# FunctionalSchematic.net
KiCad netlist of a schematic drawn in Altium Designer
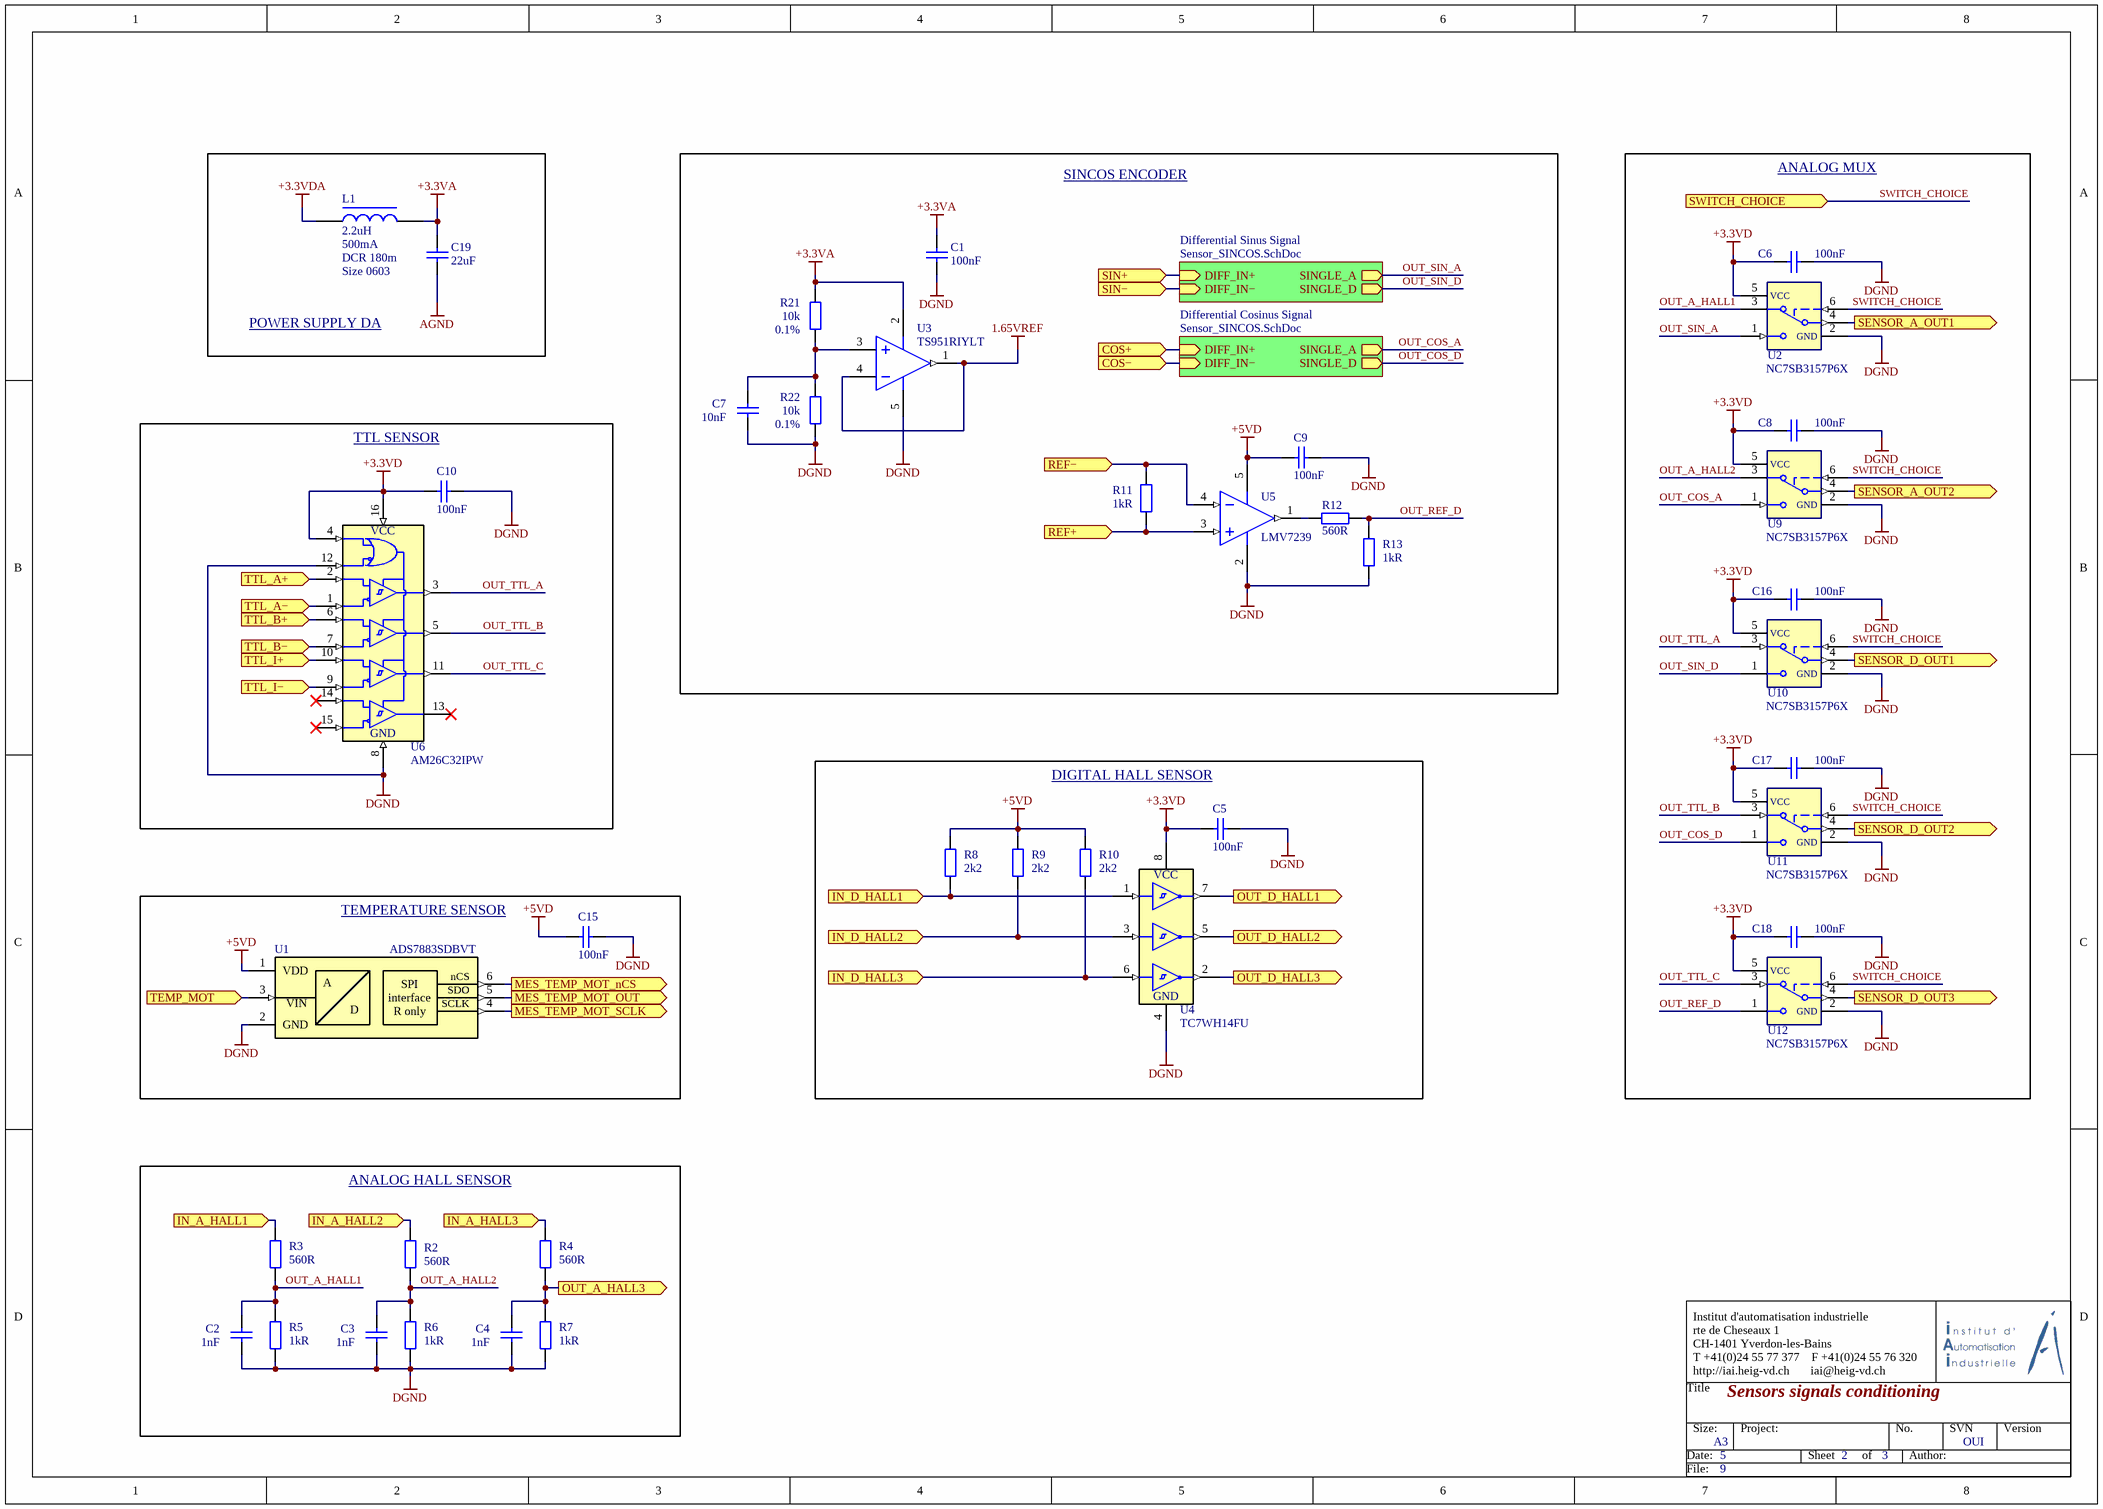
[diagram p0: FunctionalSchematic.SchDoc]

(export (version "E")
  (design (tool "Eeschema 10.0.6"))
  (components
    (comp (ref "C1")
      (value "100nF")
      (footprint "InterfaceBoard:CAPC1608X08N")
      (fields (field (name "Comment") "CAP CER 0603"))
      (libsource (lib "InterfaceBoard") (part "CAP CER 100nF 10% 10V 0603"))
    )
    (comp (ref "C2")
      (value "1nF")
      (footprint "InterfaceBoard:CAPC1608X08N")
      (description "1nF ±10% 10V Condensateurs céramique X7R 0603 (1608 métrique)")
      (fields (field (name "Comment") "CAP CER 1nF 0603"))
      (libsource (lib "InterfaceBoard") (part "CAP CER 1nF 10% 10V 0603"))
    )
    (comp (ref "C3")
      (value "1nF")
      (footprint "InterfaceBoard:CAPC1608X08N")
      (description "1nF ±10% 10V Condensateurs céramique X7R 0603 (1608 métrique)")
      (fields (field (name "Comment") "CAP CER 1nF 0603"))
      (libsource (lib "InterfaceBoard") (part "CAP CER 1nF 10% 10V 0603"))
    )
    (comp (ref "C4")
      (value "1nF")
      (footprint "InterfaceBoard:CAPC1608X08N")
      (description "1nF ±10% 10V Condensateurs céramique X7R 0603 (1608 métrique)")
      (fields (field (name "Comment") "CAP CER 1nF 0603"))
      (libsource (lib "InterfaceBoard") (part "CAP CER 1nF 10% 10V 0603"))
    )
    (comp (ref "C5")
      (value "100nF")
      (footprint "InterfaceBoard:CAPC1608X08N")
      (description "100nF ±10% 10V Condensateurs céramique X7R 0603 (1608 métrique)")
      (fields (field (name "Comment") "CAP CER 100nF 0603"))
      (libsource (lib "InterfaceBoard") (part "CAP CER 100nF 10% 10V 0603"))
    )
    (comp (ref "C6")
      (value "100nF")
      (footprint "InterfaceBoard:CAPC1608X08N")
      (description "100nF ±10% 10V Condensateurs céramique X7R 0603 (1608 métrique)")
      (fields (field (name "Comment") "CAP CER 100nF 0603"))
      (libsource (lib "InterfaceBoard") (part "CAP CER 100nF 10% 10V 0603"))
    )
    (comp (ref "C7")
      (value "10nF")
      (footprint "InterfaceBoard:CAPC1608X08N")
      (fields (field (name "Comment") "CAP CER 0603"))
      (libsource (lib "InterfaceBoard") (part "CAP CER 10nF 10% 10V 0603"))
    )
    (comp (ref "C8")
      (value "100nF")
      (footprint "InterfaceBoard:CAPC1608X08N")
      (description "100nF ±10% 10V Condensateurs céramique X7R 0603 (1608 métrique)")
      (fields (field (name "Comment") "CAP CER 100nF 0603"))
      (libsource (lib "InterfaceBoard") (part "CAP CER 100nF 10% 10V 0603"))
    )
    (comp (ref "C9")
      (value "100nF")
      (footprint "InterfaceBoard:CAPC1608X08N")
      (description "100nF ±10% 10V Condensateurs céramique X7R 0603 (1608 métrique)")
      (fields (field (name "Comment") "CAP CER 100nF 0603"))
      (libsource (lib "InterfaceBoard") (part "CAP CER 100nF 10% 10V 0603"))
    )
    (comp (ref "C10")
      (value "100nF")
      (footprint "InterfaceBoard:CAPC1608X08N")
      (description "100nF ±10% 10V Condensateurs céramique X7R 0603 (1608 métrique)")
      (fields (field (name "Comment") "CAP CER 100nF 0603"))
      (libsource (lib "InterfaceBoard") (part "CAP CER 100nF 10% 10V 0603"))
    )
    (comp (ref "C15")
      (value "100nF")
      (footprint "InterfaceBoard:CAPC1608X08N")
      (description "100nF ±10% 10V Condensateurs céramique X7R 0603 (1608 métrique)")
      (fields (field (name "Comment") "CAP CER 100nF 0603"))
      (libsource (lib "InterfaceBoard") (part "CAP CER 100nF 10% 10V 0603"))
    )
    (comp (ref "C16")
      (value "100nF")
      (footprint "InterfaceBoard:CAPC1608X08N")
      (description "100nF ±10% 10V Condensateurs céramique X7R 0603 (1608 métrique)")
      (fields (field (name "Comment") "CAP CER 100nF 0603"))
      (libsource (lib "InterfaceBoard") (part "CAP CER 100nF 10% 10V 0603"))
    )
    (comp (ref "C17")
      (value "100nF")
      (footprint "InterfaceBoard:CAPC1608X08N")
      (description "100nF ±10% 10V Condensateurs céramique X7R 0603 (1608 métrique)")
      (fields (field (name "Comment") "CAP CER 100nF 0603"))
      (libsource (lib "InterfaceBoard") (part "CAP CER 100nF 10% 10V 0603"))
    )
    (comp (ref "C18")
      (value "100nF")
      (footprint "InterfaceBoard:CAPC1608X08N")
      (description "100nF ±10% 10V Condensateurs céramique X7R 0603 (1608 métrique)")
      (fields (field (name "Comment") "CAP CER 100nF 0603"))
      (libsource (lib "InterfaceBoard") (part "CAP CER 100nF 10% 10V 0603"))
    )
    (comp (ref "C19")
      (value "22uF")
      (footprint "PowerBoard:CAPC1608X08N")
      (description "22µF ±20% 6,3V Condensateurs céramique X5R 0603 (1608 métrique)")
      (fields (field (name "Comment") "CAP CER 22uF 0603"))
      (libsource (lib "PowerBoard") (part "CAP CER 22uF 20% 6V3 0603"))
    )
    (comp (ref "L1")
      (value "2.2uH")
      (footprint "InterfaceBoard:INDC1608X10N")
      (fields
        (field (name "CURRENT") "500mA")
        (field (name "DCR") "DCR 180m")
        (field (name "SIZE") "Size 0603")
        (field (name "Comment") "IND SMD 2.2uH 0603")
      )
      (libsource (lib "CommandBoard") (part "IND SMD 2.2uH 0603"))
    )
    (comp (ref "R2")
      (value "560R")
      (footprint "InterfaceBoard:RESC1508X04N")
      (description "560 Ohms ±1% 0,1W, 1/10W Pavé résistif 0603 (1608 métrique) AutomobileAEC-Q200 Couche épaisse")
      (fields (field (name "Comment") "RES SMD 560R 0603"))
      (libsource (lib "InterfaceBoard") (part "RES SMD 560 OHM 0.1% 1/10W 0603"))
    )
    (comp (ref "R3")
      (value "560R")
      (footprint "InterfaceBoard:RESC1508X04N")
      (description "560 Ohms ±1% 0,1W, 1/10W Pavé résistif 0603 (1608 métrique) AutomobileAEC-Q200 Couche épaisse")
      (fields (field (name "Comment") "RES SMD 560R 0603"))
      (libsource (lib "InterfaceBoard") (part "RES SMD 560 OHM 0.1% 1/10W 0603"))
    )
    (comp (ref "R4")
      (value "560R")
      (footprint "InterfaceBoard:RESC1508X04N")
      (description "560 Ohms ±1% 0,1W, 1/10W Pavé résistif 0603 (1608 métrique) AutomobileAEC-Q200 Couche épaisse")
      (fields (field (name "Comment") "RES SMD 560R 0603"))
      (libsource (lib "InterfaceBoard") (part "RES SMD 560 OHM 0.1% 1/10W 0603"))
    )
    (comp (ref "R5")
      (value "1kR")
      (footprint "InterfaceBoard:RESC1508X04N")
      (description "1 kOhms ±1% 0,1W, 1/10W Pavé résistif 0603 (1608 métrique) AutomobileAEC-Q200 Couche épaisse")
      (fields (field (name "Comment") "RES SMD 1K 0603"))
      (libsource (lib "InterfaceBoard") (part "RES SMD 1K OHM 1% 1/10W 0603"))
    )
    (comp (ref "R6")
      (value "1kR")
      (footprint "InterfaceBoard:RESC1508X04N")
      (description "1 kOhms ±1% 0,1W, 1/10W Pavé résistif 0603 (1608 métrique) AutomobileAEC-Q200 Couche épaisse")
      (fields (field (name "Comment") "RES SMD 1K 0603"))
      (libsource (lib "InterfaceBoard") (part "RES SMD 1K OHM 1% 1/10W 0603"))
    )
    (comp (ref "R7")
      (value "1kR")
      (footprint "InterfaceBoard:RESC1508X04N")
      (description "1 kOhms ±1% 0,1W, 1/10W Pavé résistif 0603 (1608 métrique) AutomobileAEC-Q200 Couche épaisse")
      (fields (field (name "Comment") "RES SMD 1K 0603"))
      (libsource (lib "InterfaceBoard") (part "RES SMD 1K OHM 1% 1/10W 0603"))
    )
    (comp (ref "R8")
      (value "2k2")
      (footprint "InterfaceBoard:RESC1508X04N")
      (description "2,2 kOhms ±1% 0,1W, 1/10W Pavé résistif 0603 (1608 métrique) AutomobileAEC-Q200 Couche épaisse")
      (fields (field (name "Comment") "RES SMD 2K2 0603"))
      (libsource (lib "InterfaceBoard") (part "RES SMD 2K2 OHM 1% 1/10W 0603"))
    )
    (comp (ref "R9")
      (value "2k2")
      (footprint "InterfaceBoard:RESC1508X04N")
      (description "2,2 kOhms ±1% 0,1W, 1/10W Pavé résistif 0603 (1608 métrique) AutomobileAEC-Q200 Couche épaisse")
      (fields (field (name "Comment") "RES SMD 2K2 0603"))
      (libsource (lib "InterfaceBoard") (part "RES SMD 2K2 OHM 1% 1/10W 0603"))
    )
    (comp (ref "R10")
      (value "2k2")
      (footprint "InterfaceBoard:RESC1508X04N")
      (description "2,2 kOhms ±1% 0,1W, 1/10W Pavé résistif 0603 (1608 métrique) AutomobileAEC-Q200 Couche épaisse")
      (fields (field (name "Comment") "RES SMD 2K2 0603"))
      (libsource (lib "InterfaceBoard") (part "RES SMD 2K2 OHM 1% 1/10W 0603"))
    )
    (comp (ref "R11")
      (value "1kR")
      (footprint "InterfaceBoard:RESC1508X04N")
      (description "1 kOhms ±1% 0,1W, 1/10W Pavé résistif 0603 (1608 métrique) AutomobileAEC-Q200 Couche épaisse")
      (fields (field (name "Comment") "RES SMD 1K 0603"))
      (libsource (lib "") (part "RES SMD 1K OHM 1% 1/10W 0603_1"))
    )
    (comp (ref "R12")
      (value "560R")
      (footprint "InterfaceBoard:RESC1508X04N")
      (description "560 Ohms ±1% 0,1W, 1/10W Pavé résistif 0603 (1608 métrique) AutomobileAEC-Q200 Couche épaisse")
      (fields (field (name "Comment") "RES SMD 560R 0603"))
      (libsource (lib "") (part "RES SMD 560 OHM 0.1% 1/10W 0603_1"))
    )
    (comp (ref "R13")
      (value "1kR")
      (footprint "InterfaceBoard:RESC1508X04N")
      (description "1 kOhms ±1% 0,1W, 1/10W Pavé résistif 0603 (1608 métrique) AutomobileAEC-Q200 Couche épaisse")
      (fields (field (name "Comment") "RES SMD 1K 0603"))
      (libsource (lib "InterfaceBoard") (part "RES SMD 1K OHM 1% 1/10W 0603"))
    )
    (comp (ref "R21")
      (value "10k")
      (footprint "InterfaceBoard:RESC1508X04N")
      (description "10 kOhms ±0,1% 0,1W, 1/10W Pavé résistif 0603 (1608 métrique) AutomobileAEC-Q200 Couche mince")
      (fields (field (name "TOLERANCE") "0.1%") (field (name "Comment") "RES SMD 0603"))
      (libsource (lib "InterfaceBoard") (part "RES SMD 10K OHM 1% 1/10W 0603"))
    )
    (comp (ref "R22")
      (value "10k")
      (footprint "InterfaceBoard:RESC1508X04N")
      (description "10 kOhms ±0,1% 0,1W, 1/10W Pavé résistif 0603 (1608 métrique) AutomobileAEC-Q200 Couche mince")
      (fields (field (name "TOLERANCE") "0.1%") (field (name "Comment") "RES SMD 0603"))
      (libsource (lib "InterfaceBoard") (part "RES SMD 10K OHM 1% 1/10W 0603"))
    )
    (comp (ref "U1")
      (value "ADS7883SDBVT")
      (footprint "InterfaceBoard:SOT95P280X145-6N")
      (description "12 Bits, convertisseur analogique-numérique 1 Entrée 1 SAR SOT-23-6")
      (fields (field (name "Comment") "IC ADC 12BIT"))
      (libsource (lib "InterfaceBoard") (part "IC ADC 12BIT SAR SOT23-6"))
    )
    (comp (ref "U2")
      (value "NC7SB3157P6X")
      (footprint "InterfaceBoard:SOT95P280X145-6N")
      (description "1 Circuits, circuit intégré, commutateur 2:1 15Ohms SC-88 (SC-70-6)")
      (fields (field (name "Comment") "Analog Switch 2:1 1ch"))
      (libsource (lib "InterfaceBoard") (part "IC SWITCH SPDT"))
    )
    (comp (ref "U3")
      (value "TS951RIYLT")
      (footprint "InterfaceBoard:SOT95P280X145-5N")
      (description "CMOS Amplificateurs 1 Circuits Pôle à pôle SOT-23-5")
      (fields (field (name "Comment") "OPAMP 1 CIRCUIT"))
      (libsource (lib "InterfaceBoard") (part "IC OPAMP GP 1 CIRCUIT SOT23-5"))
    )
    (comp (ref "U4")
      (value "TC7WH14FU")
      (footprint "InterfaceBoard:TSSOP50P310X100-8N")
      (description "Inverseur IC 3 Canal US8")
      (fields (field (name "Comment") "IC INVERTER 3CH"))
      (libsource (lib "InterfaceBoard") (part "IC INVERTER 3CH 3-INP US8"))
    )
    (comp (ref "U5")
      (value "LMV7239")
      (footprint "InterfaceBoard:SOT95P280X145-5N")
      (description "Comparateurs Usage général Pousser-tirer, rail-à-rail SOT-23-5")
      (fields (field (name "Comment") "COMP 1 CIRCUIT"))
      (libsource (lib "InterfaceBoard") (part "IC COMP PUSH-PULL 1 CIRCUIT SOT-23-5"))
    )
    (comp (ref "U6")
      (value "AM26C32IPW")
      (footprint "InterfaceBoard:TSOP65P640X120-16N")
      (description "Récepteur 0/4 RS422, RS423 16-TSSOP")
      (fields (field (name "Comment") "IC RECEIVER 0/4"))
      (libsource (lib "InterfaceBoard") (part "IC RECEIVER 0/4 16TSSOP"))
    )
    (comp (ref "U9")
      (value "NC7SB3157P6X")
      (footprint "InterfaceBoard:SOT95P280X145-6N")
      (description "1 Circuits, circuit intégré, commutateur 2:1 15Ohms SC-88 (SC-70-6)")
      (fields (field (name "Comment") "Analog Switch 2:1 1ch"))
      (libsource (lib "InterfaceBoard") (part "IC SWITCH SPDT"))
    )
    (comp (ref "U10")
      (value "NC7SB3157P6X")
      (footprint "InterfaceBoard:SOT95P280X145-6N")
      (description "1 Circuits, circuit intégré, commutateur 2:1 15Ohms SC-88 (SC-70-6)")
      (fields (field (name "Comment") "Analog Switch 2:1 1ch"))
      (libsource (lib "InterfaceBoard") (part "IC SWITCH SPDT"))
    )
    (comp (ref "U11")
      (value "NC7SB3157P6X")
      (footprint "InterfaceBoard:SOT95P280X145-6N")
      (description "1 Circuits, circuit intégré, commutateur 2:1 15Ohms SC-88 (SC-70-6)")
      (fields (field (name "Comment") "Analog Switch 2:1 1ch"))
      (libsource (lib "InterfaceBoard") (part "IC SWITCH SPDT"))
    )
    (comp (ref "U12")
      (value "NC7SB3157P6X")
      (footprint "InterfaceBoard:SOT95P280X145-6N")
      (description "1 Circuits, circuit intégré, commutateur 2:1 15Ohms SC-88 (SC-70-6)")
      (fields (field (name "Comment") "Analog Switch 2:1 1ch"))
      (libsource (lib "InterfaceBoard") (part "IC SWITCH SPDT"))
    )
  )
  (nets
    (net (code "1") (name "+3.3VA") (class "Default")
      (node (ref "C1") (pin "1") (pinfunction "1_1") (pintype "passive"))
      (node (ref "C19") (pin "2") (pinfunction "2_2") (pintype "passive"))
      (node (ref "L1") (pin "2") (pinfunction "2_2") (pintype "passive"))
      (node (ref "R21") (pin "2") (pinfunction "2_2") (pintype "passive"))
      (node (ref "U3") (pin "2") (pinfunction "IN-_2") (pintype "power_in"))
    )
    (net (code "2") (name "+3.3VD") (class "Default")
      (node (ref "C10") (pin "2") (pinfunction "2_2") (pintype "passive"))
      (node (ref "C16") (pin "1") (pinfunction "1_1") (pintype "passive"))
      (node (ref "C17") (pin "1") (pinfunction "1_1") (pintype "passive"))
      (node (ref "C18") (pin "1") (pinfunction "1_1") (pintype "passive"))
      (node (ref "C5") (pin "2") (pinfunction "2_2") (pintype "passive"))
      (node (ref "C6") (pin "1") (pinfunction "1_1") (pintype "passive"))
      (node (ref "C8") (pin "1") (pinfunction "1_1") (pintype "passive"))
      (node (ref "U10") (pin "5") (pinfunction "VCC_5") (pintype "power_in"))
      (node (ref "U11") (pin "5") (pinfunction "VCC_5") (pintype "power_in"))
      (node (ref "U12") (pin "5") (pinfunction "VCC_5") (pintype "power_in"))
      (node (ref "U2") (pin "5") (pinfunction "VCC_5") (pintype "power_in"))
      (node (ref "U4") (pin "8") (pintype "power_in"))
      (node (ref "U6") (pin "16") (pintype "input"))
      (node (ref "U6") (pin "4") (pintype "input"))
      (node (ref "U9") (pin "5") (pinfunction "VCC_5") (pintype "power_in"))
    )
    (net (code "3") (name "+3.3VDA") (class "Default")
      (node (ref "L1") (pin "1") (pinfunction "1_1") (pintype "passive"))
    )
    (net (code "4") (name "+5VD") (class "Default")
      (node (ref "C15") (pin "2") (pinfunction "2_2") (pintype "passive"))
      (node (ref "C9") (pin "1") (pinfunction "1_1") (pintype "passive"))
      (node (ref "R10") (pin "2") (pinfunction "2_2") (pintype "passive"))
      (node (ref "R8") (pin "2") (pinfunction "2_2") (pintype "passive"))
      (node (ref "R9") (pin "2") (pinfunction "2_2") (pintype "passive"))
      (node (ref "U1") (pin "1") (pinfunction "VDD_1") (pintype "power_in"))
      (node (ref "U5") (pin "5") (pinfunction "IN-_5") (pintype "power_in"))
    )
    (net (code "7") (name "/IN_A_HALL1") (class "Default")
      (node (ref "R3") (pin "2") (pinfunction "2_2") (pintype "passive"))
    )
    (net (code "8") (name "/IN_A_HALL2") (class "Default")
      (node (ref "R2") (pin "2") (pinfunction "2_2") (pintype "passive"))
    )
    (net (code "9") (name "/IN_A_HALL3") (class "Default")
      (node (ref "R4") (pin "2") (pinfunction "2_2") (pintype "passive"))
    )
    (net (code "10") (name "/IN_D_HALL1") (class "Default")
      (node (ref "R8") (pin "1") (pinfunction "1_1") (pintype "passive"))
      (node (ref "U4") (pin "1") (pintype "input"))
    )
    (net (code "11") (name "/IN_D_HALL2") (class "Default")
      (node (ref "R9") (pin "1") (pinfunction "1_1") (pintype "passive"))
      (node (ref "U4") (pin "3") (pintype "input"))
    )
    (net (code "12") (name "/IN_D_HALL3") (class "Default")
      (node (ref "R10") (pin "1") (pinfunction "1_1") (pintype "passive"))
      (node (ref "U4") (pin "6") (pintype "input"))
    )
    (net (code "13") (name "/MES_TEMP_MOT_OUT") (class "Default")
      (node (ref "U1") (pin "5") (pinfunction "nCS_5") (pintype "output"))
    )
    (net (code "14") (name "/MES_TEMP_MOT_SCLK") (class "Default")
      (node (ref "U1") (pin "4") (pinfunction "SCLK_4") (pintype "output"))
    )
    (net (code "15") (name "/MES_TEMP_MOT_nCS") (class "Default")
      (node (ref "U1") (pin "6") (pinfunction "DOUT_6") (pintype "output"))
    )
    (net (code "16") (name "/OUT_A_HALL1") (class "Default")
      (node (ref "C2") (pin "2") (pinfunction "2_2") (pintype "passive"))
      (node (ref "R3") (pin "1") (pinfunction "1_1") (pintype "passive"))
      (node (ref "R5") (pin "2") (pinfunction "2_2") (pintype "passive"))
      (node (ref "U2") (pin "3") (pinfunction "S1A_3") (pintype "input"))
    )
    (net (code "17") (name "/OUT_A_HALL2") (class "Default")
      (node (ref "C3") (pin "2") (pinfunction "2_2") (pintype "passive"))
      (node (ref "R2") (pin "1") (pinfunction "1_1") (pintype "passive"))
      (node (ref "R6") (pin "2") (pinfunction "2_2") (pintype "passive"))
      (node (ref "U9") (pin "3") (pinfunction "S1A_3") (pintype "input"))
    )
    (net (code "18") (name "/OUT_A_HALL3") (class "Default")
      (node (ref "C4") (pin "2") (pinfunction "2_2") (pintype "passive"))
      (node (ref "R4") (pin "1") (pinfunction "1_1") (pintype "passive"))
      (node (ref "R7") (pin "2") (pinfunction "2_2") (pintype "passive"))
    )
    (net (code "19") (name "/OUT_COS_A") (class "Default")
      (node (ref "U9") (pin "1") (pinfunction "S2A_1") (pintype "power_in"))
    )
    (net (code "20") (name "/OUT_COS_D") (class "Default")
      (node (ref "U11") (pin "1") (pinfunction "S2A_1") (pintype "power_in"))
    )
    (net (code "21") (name "/OUT_D_HALL1") (class "Default") (node (ref "U4") (pin "7") (pintype "output")))
    (net (code "22") (name "/OUT_D_HALL2") (class "Default") (node (ref "U4") (pin "5") (pintype "output")))
    (net (code "23") (name "/OUT_D_HALL3") (class "Default") (node (ref "U4") (pin "2") (pintype "output")))
    (net (code "24") (name "/OUT_REF_D") (class "Default")
      (node (ref "R12") (pin "1") (pinfunction "1_1") (pintype "passive"))
      (node (ref "R13") (pin "2") (pinfunction "2_2") (pintype "passive"))
      (node (ref "U12") (pin "1") (pinfunction "S2A_1") (pintype "power_in"))
    )
    (net (code "25") (name "/OUT_SIN_A") (class "Default")
      (node (ref "U2") (pin "1") (pinfunction "S2A_1") (pintype "power_in"))
    )
    (net (code "26") (name "/OUT_SIN_D") (class "Default")
      (node (ref "U10") (pin "1") (pinfunction "S2A_1") (pintype "power_in"))
    )
    (net (code "27") (name "/OUT_TTL_A") (class "Default")
      (node (ref "U10") (pin "3") (pinfunction "S1A_3") (pintype "input"))
      (node (ref "U6") (pin "3") (pintype "output"))
    )
    (net (code "28") (name "/OUT_TTL_B") (class "Default")
      (node (ref "U11") (pin "3") (pinfunction "S1A_3") (pintype "input"))
      (node (ref "U6") (pin "5") (pintype "output"))
    )
    (net (code "29") (name "/OUT_TTL_C") (class "Default")
      (node (ref "U12") (pin "3") (pinfunction "S1A_3") (pintype "input"))
      (node (ref "U6") (pin "11") (pintype "output"))
    )
    (net (code "30") (name "/REF+") (class "Default")
      (node (ref "R11") (pin "2") (pinfunction "2_2") (pintype "passive"))
      (node (ref "U5") (pin "3") (pinfunction "IN+_3") (pintype "input"))
    )
    (net (code "31") (name "/REF−") (class "Default")
      (node (ref "R11") (pin "1") (pinfunction "1_1") (pintype "passive"))
      (node (ref "U5") (pin "4") (pinfunction "IN-_4") (pintype "input"))
    )
    (net (code "32") (name "/SENSOR_A_OUT1") (class "Default")
      (node (ref "U2") (pin "4") (pinfunction "D1_4") (pintype "output"))
    )
    (net (code "33") (name "/SENSOR_A_OUT2") (class "Default")
      (node (ref "U9") (pin "4") (pinfunction "D1_4") (pintype "output"))
    )
    (net (code "34") (name "/SENSOR_D_OUT1") (class "Default")
      (node (ref "U10") (pin "4") (pinfunction "D1_4") (pintype "output"))
    )
    (net (code "35") (name "/SENSOR_D_OUT2") (class "Default")
      (node (ref "U11") (pin "4") (pinfunction "D1_4") (pintype "output"))
    )
    (net (code "36") (name "/SENSOR_D_OUT3") (class "Default")
      (node (ref "U12") (pin "4") (pinfunction "D1_4") (pintype "output"))
    )
    (net (code "39") (name "/SWITCH_CHOICE") (class "Default")
      (node (ref "U10") (pin "6") (pinfunction "IN1_6") (pintype "input"))
      (node (ref "U11") (pin "6") (pinfunction "IN1_6") (pintype "input"))
      (node (ref "U12") (pin "6") (pinfunction "IN1_6") (pintype "input"))
      (node (ref "U2") (pin "6") (pinfunction "IN1_6") (pintype "input"))
      (node (ref "U9") (pin "6") (pinfunction "IN1_6") (pintype "input"))
    )
    (net (code "40") (name "/TEMP_MOT") (class "Default")
      (node (ref "U1") (pin "3") (pinfunction "VIN_3") (pintype "input"))
    )
    (net (code "41") (name "/TTL_A+") (class "Default") (node (ref "U6") (pin "2") (pintype "input")))
    (net (code "42") (name "/TTL_A−") (class "Default") (node (ref "U6") (pin "1") (pintype "input")))
    (net (code "43") (name "/TTL_B+") (class "Default") (node (ref "U6") (pin "6") (pintype "input")))
    (net (code "44") (name "/TTL_B−") (class "Default") (node (ref "U6") (pin "7") (pintype "input")))
    (net (code "45") (name "/TTL_I+") (class "Default") (node (ref "U6") (pin "10") (pintype "input")))
    (net (code "46") (name "/TTL_I−") (class "Default") (node (ref "U6") (pin "9") (pintype "input")))
    (net (code "47") (name "1.65VREF") (class "Default")
      (node (ref "U3") (pin "1") (pinfunction "OUT_1") (pintype "output"))
      (node (ref "U3") (pin "4") (pinfunction "IN-_4") (pintype "passive"))
    )
    (net (code "48") (name "AGND") (class "Default")
      (node (ref "C19") (pin "1") (pinfunction "1_1") (pintype "passive"))
    )
    (net (code "49") (name "DGND") (class "Default")
      (node (ref "C1") (pin "2") (pinfunction "2_2") (pintype "passive"))
      (node (ref "C10") (pin "1") (pinfunction "1_1") (pintype "passive"))
      (node (ref "C15") (pin "1") (pinfunction "1_1") (pintype "passive"))
      (node (ref "C16") (pin "2") (pinfunction "2_2") (pintype "passive"))
      (node (ref "C17") (pin "2") (pinfunction "2_2") (pintype "passive"))
      (node (ref "C18") (pin "2") (pinfunction "2_2") (pintype "passive"))
      (node (ref "C2") (pin "1") (pinfunction "1_1") (pintype "passive"))
      (node (ref "C3") (pin "1") (pinfunction "1_1") (pintype "passive"))
      (node (ref "C4") (pin "1") (pinfunction "1_1") (pintype "passive"))
      (node (ref "C5") (pin "1") (pinfunction "1_1") (pintype "passive"))
      (node (ref "C6") (pin "2") (pinfunction "2_2") (pintype "passive"))
      (node (ref "C7") (pin "1") (pinfunction "1_1") (pintype "passive"))
      (node (ref "C8") (pin "2") (pinfunction "2_2") (pintype "passive"))
      (node (ref "C9") (pin "2") (pinfunction "2_2") (pintype "passive"))
      (node (ref "R13") (pin "1") (pinfunction "1_1") (pintype "passive"))
      (node (ref "R22") (pin "1") (pinfunction "1_1") (pintype "passive"))
      (node (ref "R5") (pin "1") (pinfunction "1_1") (pintype "passive"))
      (node (ref "R6") (pin "1") (pinfunction "1_1") (pintype "passive"))
      (node (ref "R7") (pin "1") (pinfunction "1_1") (pintype "passive"))
      (node (ref "U1") (pin "2") (pinfunction "GND_2") (pintype "power_in"))
      (node (ref "U10") (pin "2") (pinfunction "GND_2") (pintype "power_in"))
      (node (ref "U11") (pin "2") (pinfunction "GND_2") (pintype "power_in"))
      (node (ref "U12") (pin "2") (pinfunction "GND_2") (pintype "power_in"))
      (node (ref "U2") (pin "2") (pinfunction "GND_2") (pintype "power_in"))
      (node (ref "U3") (pin "5") (pinfunction "IN-_5") (pintype "power_in"))
      (node (ref "U4") (pin "4") (pintype "power_in"))
      (node (ref "U5") (pin "2") (pinfunction "IN-_2") (pintype "power_in"))
      (node (ref "U6") (pin "12") (pintype "input"))
      (node (ref "U6") (pin "8") (pintype "input"))
      (node (ref "U9") (pin "2") (pinfunction "GND_2") (pintype "power_in"))
    )
    (net (code "50") (name "Net-(U3-IN+)") (class "Default")
      (node (ref "C7") (pin "2") (pinfunction "2_2") (pintype "passive"))
      (node (ref "R21") (pin "1") (pinfunction "1_1") (pintype "passive"))
      (node (ref "R22") (pin "2") (pinfunction "2_2") (pintype "passive"))
      (node (ref "U3") (pin "3") (pinfunction "IN+_3") (pintype "passive"))
    )
    (net (code "51") (name "Net-(U5-OUT)") (class "Default")
      (node (ref "R12") (pin "2") (pinfunction "2_2") (pintype "passive"))
      (node (ref "U5") (pin "1") (pinfunction "OUT_1") (pintype "output"))
    )
    (net (code "52") (name "unconnected-(U6-Pad13)") (class "Default")
      (node (ref "U6") (pin "13") (pintype "power_in+no_connect"))
    )
    (net (code "53") (name "unconnected-(U6-Pad14)") (class "Default")
      (node (ref "U6") (pin "14") (pintype "input+no_connect"))
    )
    (net (code "54") (name "unconnected-(U6-Pad15)") (class "Default")
      (node (ref "U6") (pin "15") (pintype "input+no_connect"))
    )
  )
)
